# LidHeater_NTC_withDril.net
KiCad netlist of a schematic drawn in EAGLE
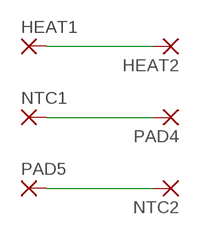
[diagram p0: schematic, sheet 1]

(export (version "E")
  (design (tool "Eeschema 10.0.6"))
  (components
    (comp (ref "HEAT1")
      (value "SMD5")
      (footprint "eagle-import:SMD2,54-5,08")
      (libsource (lib "eagle-import") (part "SMD5"))
    )
    (comp (ref "HEAT2")
      (value "SMD5")
      (footprint "eagle-import:SMD2,54-5,08")
      (libsource (lib "eagle-import") (part "SMD5"))
    )
    (comp (ref "NTC1")
      (value "SMD5")
      (footprint "eagle-import:SMD2,54-5,08")
      (libsource (lib "eagle-import") (part "SMD5"))
    )
    (comp (ref "NTC2")
      (value "SMD5")
      (footprint "eagle-import:SMD2,54-5,08")
      (libsource (lib "eagle-import") (part "SMD5"))
    )
    (comp (ref "PAD4")
      (value "SMD5")
      (footprint "eagle-import:SMD2,54-5,08")
      (libsource (lib "eagle-import") (part "SMD5"))
    )
    (comp (ref "PAD5")
      (value "SMD5")
      (footprint "eagle-import:SMD2,54-5,08")
      (libsource (lib "eagle-import") (part "SMD5"))
    )
  )
  (nets
    (net (code "1") (name "Net-(HEAT1-P)") (class "Default")
      (node (ref "HEAT1") (pin "1") (pinfunction "P_1") (pintype "passive"))
      (node (ref "HEAT2") (pin "1") (pinfunction "P_1") (pintype "passive"))
    )
    (net (code "2") (name "Net-(NTC1-P)") (class "Default")
      (node (ref "NTC1") (pin "1") (pinfunction "P_1") (pintype "passive"))
      (node (ref "PAD4") (pin "1") (pinfunction "P_1") (pintype "passive"))
    )
    (net (code "3") (name "Net-(NTC2-P)") (class "Default")
      (node (ref "NTC2") (pin "1") (pinfunction "P_1") (pintype "passive"))
      (node (ref "PAD5") (pin "1") (pinfunction "P_1") (pintype "passive"))
    )
  )
)
